# SCH_WINGLET_DEBUG.net
KiCad netlist of a schematic drawn in Altium Designer
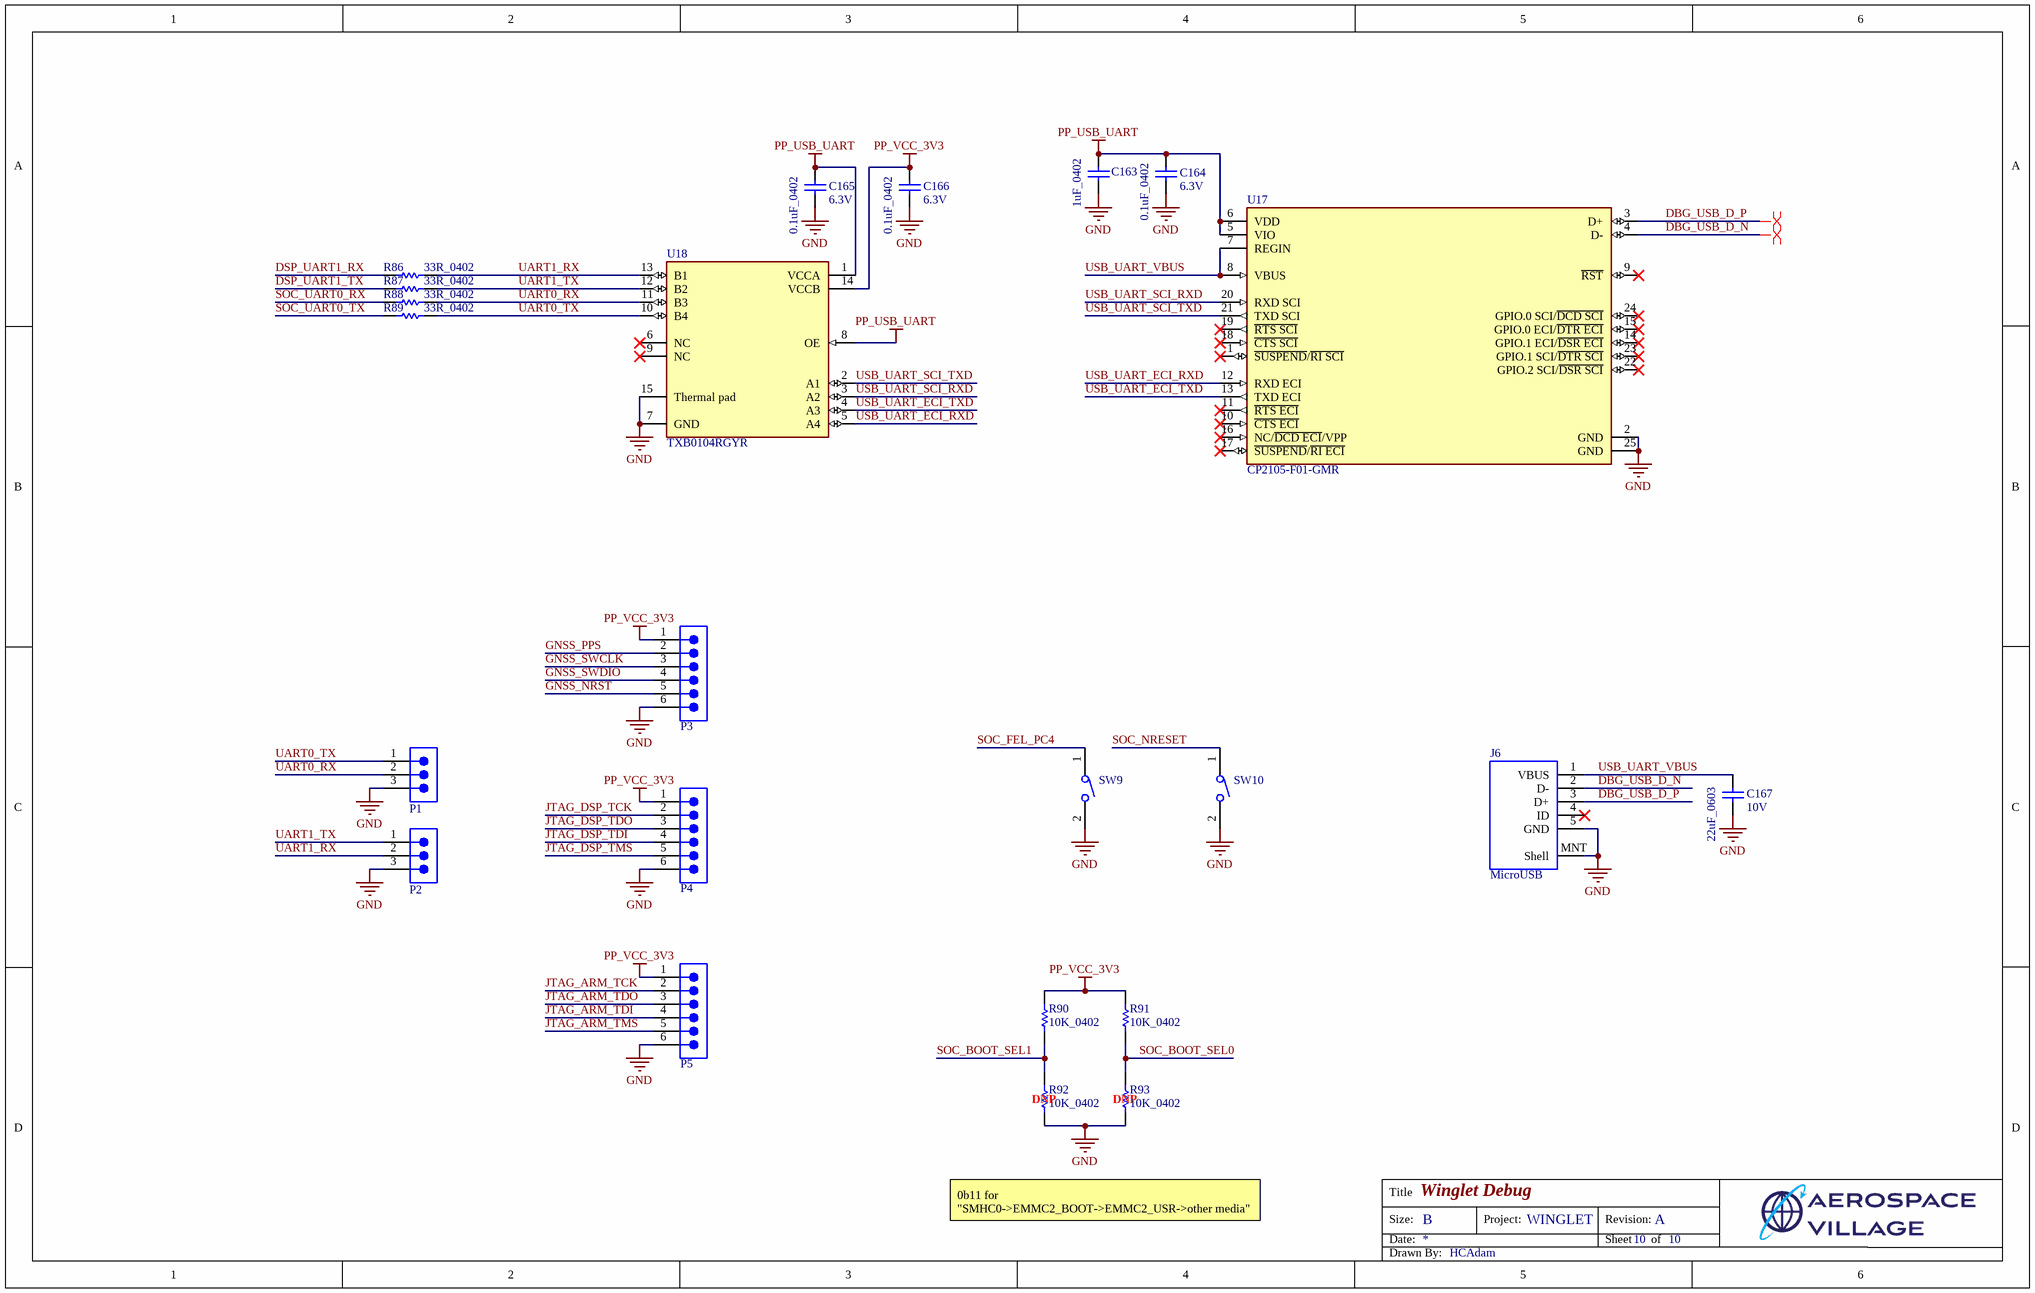
[diagram p0: SCH_WINGLET_DEBUG.SchDoc]

(export (version "E")
  (design (tool "Eeschema 10.0.6"))
  (components
    (comp (ref "C163")
      (value "1uF_0402")
      (footprint "CAPC1005X55X25NL5T10")
      (fields (field (name "TOLERANCE") "10%") (field (name "PARTNUMBER") "GRM155R60J105KE19D"))
      (libsource (lib "Altium Content Vault") (part "CAP-NP-2"))
    )
    (comp (ref "C164")
      (value "0.1uF_0402")
      (footprint "CAPC1005X56X25NL10T15")
      (description "04026D104KAT2A")
      (fields (field (name "MANUFACTURER") "AVX Interconnect / Elco") (field (name "VOLTAGE RATING") "6.3V"))
      (libsource (lib "Altium Content Vault") (part "CAP"))
    )
    (comp (ref "C165")
      (value "0.1uF_0402")
      (footprint "CAPC1005X56X25NL10T15")
      (description "04026D104KAT2A")
      (fields (field (name "MANUFACTURER") "AVX Interconnect / Elco") (field (name "VOLTAGE RATING") "6.3V"))
      (libsource (lib "Altium Content Vault") (part "CAP"))
    )
    (comp (ref "C166")
      (value "0.1uF_0402")
      (footprint "CAPC1005X56X25NL10T15")
      (description "04026D104KAT2A")
      (fields (field (name "MANUFACTURER") "AVX Interconnect / Elco") (field (name "VOLTAGE RATING") "6.3V"))
      (libsource (lib "Altium Content Vault") (part "CAP"))
    )
    (comp (ref "C167")
      (value "22uF_0603")
      (footprint "CAPC1608X100X20NL10")
      (fields
        (field (name "MANUFACTURER") "TDK")
        (field (name "TOLERANCE") "±20%")
        (field (name "PCN PART NUMBER") "MLCCPartNumberChange30/Nov/2012")
        (field (name "VOLTAGE RATING") "10V")
      )
      (libsource (lib "Altium Content Vault") (part "CAP-NP-2"))
    )
    (comp (ref "J6")
      (value "MicroUSB")
      (footprint "LCSC_MicroQTJ")
      (description "MicroQTJ MicroUSB CONN")
      (libsource (lib "DCAV32_WINGLET_SCHLIB") (part "MicroQTJ"))
    )
    (comp (ref "P1")
      (value "TSW-103-07-G-S")
      (footprint "SMTC-TSW-103-07-X-S")
      (description "0.025\" SQ Post Header, Through-hole, Vertical, -55 to 125 degC, 2.54 mm Pitch, 3-Pin, Male, RoHS")
      (fields (field (name "MANUFACTURER") "Samtec"))
      (libsource (lib "Altium Content Vault") (part "SMTC-TSW-103-X-X-S-X"))
    )
    (comp (ref "P2")
      (value "TSW-103-07-G-S")
      (footprint "SMTC-TSW-103-07-X-S")
      (description "0.025\" SQ Post Header, Through-hole, Vertical, -55 to 125 degC, 2.54 mm Pitch, 3-Pin, Male, RoHS")
      (fields (field (name "MANUFACTURER") "Samtec"))
      (libsource (lib "Altium Content Vault") (part "SMTC-TSW-103-X-X-S-X"))
    )
    (comp (ref "P3")
      (value "TSW-106-07-F-S")
      (footprint "SMTC-TSW-106-07-X-S")
      (description "0.025\" SQ Post Header, Through-hole, Vertical, -55 to 125 degC, 2.54 mm Pitch, 6-Pin, Male, RoHS")
      (fields (field (name "MANUFACTURER") "Samtec"))
      (libsource (lib "Altium Content Vault") (part "SMTC-TSW-106-X-X-S-X"))
    )
    (comp (ref "P4")
      (value "TSW-106-07-F-S")
      (footprint "SMTC-TSW-106-07-X-S")
      (description "0.025\" SQ Post Header, Through-hole, Vertical, -55 to 125 degC, 2.54 mm Pitch, 6-Pin, Male, RoHS")
      (fields (field (name "MANUFACTURER") "Samtec"))
      (libsource (lib "Altium Content Vault") (part "SMTC-TSW-106-X-X-S-X"))
    )
    (comp (ref "P5")
      (value "TSW-106-07-F-S")
      (footprint "SMTC-TSW-106-07-X-S")
      (description "0.025\" SQ Post Header, Through-hole, Vertical, -55 to 125 degC, 2.54 mm Pitch, 6-Pin, Male, RoHS")
      (fields (field (name "MANUFACTURER") "Samtec"))
      (libsource (lib "Altium Content Vault") (part "SMTC-TSW-106-X-X-S-X"))
    )
    (comp (ref "R86")
      (value "33R_0402")
      (footprint "RESC1005X40X25NL05T05")
      (description "ERJ2RKF33R0X")
      (fields (field (name "MANUFACTURER") "Panasonic"))
      (libsource (lib "Altium Content Vault") (part "RES"))
    )
    (comp (ref "R87")
      (value "33R_0402")
      (footprint "RESC1005X40X25NL05T05")
      (description "ERJ2RKF33R0X")
      (fields (field (name "MANUFACTURER") "Panasonic"))
      (libsource (lib "Altium Content Vault") (part "RES"))
    )
    (comp (ref "R88")
      (value "33R_0402")
      (footprint "RESC1005X40X25NL05T05")
      (description "ERJ2RKF33R0X")
      (fields (field (name "MANUFACTURER") "Panasonic"))
      (libsource (lib "Altium Content Vault") (part "RES"))
    )
    (comp (ref "R89")
      (value "33R_0402")
      (footprint "RESC1005X40X25NL05T05")
      (description "ERJ2RKF33R0X")
      (fields (field (name "MANUFACTURER") "Panasonic"))
      (libsource (lib "Altium Content Vault") (part "RES"))
    )
    (comp (ref "R90")
      (value "10K_0402")
      (footprint "RESC1005X40X25NL05T05")
      (fields (field (name "TOLERANCE") "1%") (field (name "MANUFACTURER") "Panasonic"))
      (libsource (lib "Altium Content Vault") (part "RES-2"))
    )
    (comp (ref "R91")
      (value "10K_0402")
      (footprint "RESC1005X40X25NL05T05")
      (fields (field (name "TOLERANCE") "1%") (field (name "MANUFACTURER") "Panasonic"))
      (libsource (lib "Altium Content Vault") (part "RES-2"))
    )
    (comp (ref "R92")
      (value "10K_0402")
      (footprint "RESC1005X40X25NL05T05")
      (fields
        (field (name "TOLERANCE") "1%")
        (field (name "MANUFACTURER") "Panasonic")
        (field (name "DNP") "DNP")
      )
      (libsource (lib "Altium Content Vault") (part "RES-2"))
    )
    (comp (ref "R93")
      (value "10K_0402")
      (footprint "RESC1005X40X25NL05T05")
      (fields
        (field (name "TOLERANCE") "1%")
        (field (name "MANUFACTURER") "Panasonic")
        (field (name "DNP") "DNP")
      )
      (libsource (lib "Altium Content Vault") (part "RES-2"))
    )
    (comp (ref "SW9")
      (value "GT-TC029B-H025-L1N")
      (footprint "LCSC_SMD_SW_SMALL")
      (description "SMD SPST Tactile Switch\r\nC843669")
      (libsource (lib "DCAV32_WINGLET_SCHLIB") (part "GT-TC029B-H025-L1N"))
    )
    (comp (ref "SW10")
      (value "GT-TC029B-H025-L1N")
      (footprint "LCSC_SMD_SW_SMALL")
      (description "SMD SPST Tactile Switch\r\nC843669")
      (libsource (lib "DCAV32_WINGLET_SCHLIB") (part "GT-TC029B-H025-L1N"))
    )
    (comp (ref "U17")
      (value "CP2105-F01-GMR")
      (footprint "FP-CP2105-F01-GMR-MFG")
      (description "IC SGL USB-DL UART BRIDGE 24QFN")
      (fields
        (field (name "MANUFACTURER") "Silicon Labs")
        (field (name "OCTOPART") "https://octopart.com/cp2105-f01-gmr-silicon+labs-19668643")
      )
      (libsource (lib "Altium Content Vault") (part "1947c35c85b0d61e04dffc410a2c8d9"))
    )
    (comp (ref "U18")
      (value "TXB0104RGYR")
      (footprint "FP-RGY0014A-MFG")
      (description "IC TRNSLTR BIDIRECTIONAL 14VQFN")
      (fields
        (field (name "MANUFACTURER") "Texas Instruments")
        (field (name "OCTOPART") "https://octopart.com/txb0104rgyr-texas+instruments-1485948")
      )
      (libsource (lib "Altium Content Vault") (part "00c1e25395d90d543401131e0a6fef8"))
    )
  )
  (nets
    (net (code "1") (name "/DBG_USB_D_N") (class "Default")
      (node (ref "J6") (pin "2") (pinfunction "D-_2") (pintype "passive"))
      (node (ref "U17") (pin "4") (pinfunction "D-_4") (pintype "bidirectional"))
    )
    (net (code "2") (name "/DBG_USB_D_P") (class "Default")
      (node (ref "J6") (pin "3") (pinfunction "D+_3") (pintype "passive"))
      (node (ref "U17") (pin "3") (pinfunction "D+_3") (pintype "bidirectional"))
    )
    (net (code "3") (name "/DSP_UART1_RX") (class "Default")
      (node (ref "R86") (pin "1") (pinfunction "1_1") (pintype "passive"))
    )
    (net (code "4") (name "/DSP_UART1_TX") (class "Default")
      (node (ref "R87") (pin "1") (pinfunction "1_1") (pintype "passive"))
    )
    (net (code "5") (name "/GNSS_NRST") (class "Default")
      (node (ref "P3") (pin "5") (pinfunction "5_5") (pintype "passive"))
    )
    (net (code "6") (name "/GNSS_PPS") (class "Default")
      (node (ref "P3") (pin "2") (pinfunction "2_2") (pintype "passive"))
    )
    (net (code "7") (name "/GNSS_SWCLK") (class "Default")
      (node (ref "P3") (pin "3") (pinfunction "3_3") (pintype "passive"))
    )
    (net (code "8") (name "/GNSS_SWDIO") (class "Default")
      (node (ref "P3") (pin "4") (pinfunction "4_4") (pintype "passive"))
    )
    (net (code "9") (name "/JTAG_ARM_TCK") (class "Default")
      (node (ref "P5") (pin "2") (pinfunction "2_2") (pintype "passive"))
    )
    (net (code "10") (name "/JTAG_ARM_TDI") (class "Default")
      (node (ref "P5") (pin "4") (pinfunction "4_4") (pintype "passive"))
    )
    (net (code "11") (name "/JTAG_ARM_TDO") (class "Default")
      (node (ref "P5") (pin "3") (pinfunction "3_3") (pintype "passive"))
    )
    (net (code "12") (name "/JTAG_ARM_TMS") (class "Default")
      (node (ref "P5") (pin "5") (pinfunction "5_5") (pintype "passive"))
    )
    (net (code "13") (name "/JTAG_DSP_TCK") (class "Default")
      (node (ref "P4") (pin "2") (pinfunction "2_2") (pintype "passive"))
    )
    (net (code "14") (name "/JTAG_DSP_TDI") (class "Default")
      (node (ref "P4") (pin "4") (pinfunction "4_4") (pintype "passive"))
    )
    (net (code "15") (name "/JTAG_DSP_TDO") (class "Default")
      (node (ref "P4") (pin "3") (pinfunction "3_3") (pintype "passive"))
    )
    (net (code "16") (name "/JTAG_DSP_TMS") (class "Default")
      (node (ref "P4") (pin "5") (pinfunction "5_5") (pintype "passive"))
    )
    (net (code "17") (name "/SOC_BOOT_SEL0") (class "Default")
      (node (ref "R91") (pin "2") (pinfunction "2_2") (pintype "passive"))
      (node (ref "R93") (pin "1") (pinfunction "1_1") (pintype "passive"))
    )
    (net (code "18") (name "/SOC_BOOT_SEL1") (class "Default")
      (node (ref "R90") (pin "2") (pinfunction "2_2") (pintype "passive"))
      (node (ref "R92") (pin "1") (pinfunction "1_1") (pintype "passive"))
    )
    (net (code "19") (name "/SOC_FEL_PC4") (class "Default") (node (ref "SW9") (pin "1") (pintype "passive")))
    (net (code "20") (name "/SOC_NRESET") (class "Default") (node (ref "SW10") (pin "1") (pintype "passive")))
    (net (code "21") (name "/SOC_UART0_RX") (class "Default")
      (node (ref "R88") (pin "1") (pinfunction "1_1") (pintype "passive"))
    )
    (net (code "22") (name "/SOC_UART0_TX") (class "Default")
      (node (ref "R89") (pin "1") (pinfunction "1_1") (pintype "passive"))
    )
    (net (code "23") (name "/UART0_RX") (class "Default")
      (node (ref "P1") (pin "2") (pinfunction "2_2") (pintype "passive"))
      (node (ref "R88") (pin "2") (pinfunction "2_2") (pintype "passive"))
      (node (ref "U18") (pin "11") (pinfunction "B3_11") (pintype "bidirectional"))
    )
    (net (code "24") (name "/UART0_TX") (class "Default")
      (node (ref "P1") (pin "1") (pinfunction "1_1") (pintype "passive"))
      (node (ref "R89") (pin "2") (pinfunction "2_2") (pintype "passive"))
      (node (ref "U18") (pin "10") (pinfunction "B4_10") (pintype "bidirectional"))
    )
    (net (code "25") (name "/UART1_RX") (class "Default")
      (node (ref "P2") (pin "2") (pinfunction "2_2") (pintype "passive"))
      (node (ref "R86") (pin "2") (pinfunction "2_2") (pintype "passive"))
      (node (ref "U18") (pin "13") (pinfunction "B1_13") (pintype "bidirectional"))
    )
    (net (code "26") (name "/UART1_TX") (class "Default")
      (node (ref "P2") (pin "1") (pinfunction "1_1") (pintype "passive"))
      (node (ref "R87") (pin "2") (pinfunction "2_2") (pintype "passive"))
      (node (ref "U18") (pin "12") (pinfunction "B2_12") (pintype "bidirectional"))
    )
    (net (code "27") (name "/USB_UART_ECI_RXD") (class "Default")
      (node (ref "U17") (pin "12") (pinfunction "RXD_ECI_12") (pintype "input"))
      (node (ref "U18") (pin "5") (pinfunction "A4_5") (pintype "bidirectional"))
    )
    (net (code "28") (name "/USB_UART_ECI_TXD") (class "Default")
      (node (ref "U17") (pin "13") (pinfunction "TXD_ECI_13") (pintype "output"))
      (node (ref "U18") (pin "4") (pinfunction "A3_4") (pintype "bidirectional"))
    )
    (net (code "29") (name "/USB_UART_SCI_RXD") (class "Default")
      (node (ref "U17") (pin "20") (pinfunction "RXD_SCI_20") (pintype "input"))
      (node (ref "U18") (pin "3") (pinfunction "A2_3") (pintype "bidirectional"))
    )
    (net (code "30") (name "/USB_UART_SCI_TXD") (class "Default")
      (node (ref "U17") (pin "21") (pinfunction "TXD_SCI_21") (pintype "output"))
      (node (ref "U18") (pin "2") (pinfunction "A1_2") (pintype "bidirectional"))
    )
    (net (code "31") (name "/USB_UART_VBUS") (class "Default")
      (node (ref "C167") (pin "2") (pinfunction "2_2") (pintype "passive"))
      (node (ref "J6") (pin "1") (pinfunction "VBUS_1") (pintype "passive"))
      (node (ref "U17") (pin "7") (pinfunction "REGIN_7") (pintype "power_in"))
      (node (ref "U17") (pin "8") (pinfunction "VBUS_8") (pintype "input"))
    )
    (net (code "32") (name "GND") (class "Default")
      (node (ref "C163") (pin "1") (pinfunction "1_1") (pintype "passive"))
      (node (ref "C164") (pin "1") (pinfunction "1_1") (pintype "passive"))
      (node (ref "C165") (pin "1") (pinfunction "1_1") (pintype "passive"))
      (node (ref "C166") (pin "1") (pinfunction "1_1") (pintype "passive"))
      (node (ref "C167") (pin "1") (pinfunction "1_1") (pintype "passive"))
      (node (ref "J6") (pin "5") (pinfunction "GND_5") (pintype "passive"))
      (node (ref "J6") (pin "MNT") (pinfunction "Shell_MNT") (pintype "passive"))
      (node (ref "P1") (pin "3") (pinfunction "3_3") (pintype "passive"))
      (node (ref "P2") (pin "3") (pinfunction "3_3") (pintype "passive"))
      (node (ref "P3") (pin "6") (pinfunction "6_6") (pintype "passive"))
      (node (ref "P4") (pin "6") (pinfunction "6_6") (pintype "passive"))
      (node (ref "P5") (pin "6") (pinfunction "6_6") (pintype "passive"))
      (node (ref "R92") (pin "2") (pinfunction "2_2") (pintype "passive"))
      (node (ref "R93") (pin "2") (pinfunction "2_2") (pintype "passive"))
      (node (ref "SW10") (pin "2") (pintype "passive"))
      (node (ref "SW9") (pin "2") (pintype "passive"))
      (node (ref "U17") (pin "2") (pinfunction "GND_2") (pintype "power_in"))
      (node (ref "U17") (pin "25") (pinfunction "GND_25") (pintype "power_in"))
      (node (ref "U18") (pin "15") (pinfunction "Thermal_pad_15") (pintype "power_in"))
      (node (ref "U18") (pin "7") (pinfunction "GND_7") (pintype "power_in"))
    )
    (net (code "33") (name "PP_USB_UART") (class "Default")
      (node (ref "C163") (pin "2") (pinfunction "2_2") (pintype "passive"))
      (node (ref "C164") (pin "2") (pinfunction "2_2") (pintype "passive"))
      (node (ref "C165") (pin "2") (pinfunction "2_2") (pintype "passive"))
      (node (ref "U17") (pin "5") (pinfunction "VIO_5") (pintype "power_in"))
      (node (ref "U17") (pin "6") (pinfunction "VDD_6") (pintype "power_in"))
      (node (ref "U18") (pin "1") (pinfunction "VCCA_1") (pintype "power_in"))
      (node (ref "U18") (pin "8") (pinfunction "OE_8") (pintype "input"))
    )
    (net (code "34") (name "PP_VCC_3V3") (class "Default")
      (node (ref "C166") (pin "2") (pinfunction "2_2") (pintype "passive"))
      (node (ref "P3") (pin "1") (pinfunction "1_1") (pintype "passive"))
      (node (ref "P4") (pin "1") (pinfunction "1_1") (pintype "passive"))
      (node (ref "P5") (pin "1") (pinfunction "1_1") (pintype "passive"))
      (node (ref "R90") (pin "1") (pinfunction "1_1") (pintype "passive"))
      (node (ref "R91") (pin "1") (pinfunction "1_1") (pintype "passive"))
      (node (ref "U18") (pin "14") (pinfunction "VCCB_14") (pintype "power_in"))
    )
    (net (code "35") (name "unconnected-(J6-ID-Pad4)") (class "Default")
      (node (ref "J6") (pin "4") (pinfunction "ID_4") (pintype "passive+no_connect"))
    )
    (net (code "36") (name "unconnected-(U17-GPIO.0_ECI{slash}~{DTR_ECI}-Pad15)") (class "Default")
      (node (ref "U17") (pin "15") (pinfunction "GPIO.0_ECI/~{DTR_ECI}_15") (pintype "bidirectional+no_connect"))
    )
    (net (code "37") (name "unconnected-(U17-GPIO.0_SCI{slash}~{DCD_SCI}-Pad24)") (class "Default")
      (node (ref "U17") (pin "24") (pinfunction "GPIO.0_SCI/~{DCD_SCI}_24") (pintype "bidirectional+no_connect"))
    )
    (net (code "38") (name "unconnected-(U17-GPIO.1_ECI{slash}~{DSR_ECI}-Pad14)") (class "Default")
      (node (ref "U17") (pin "14") (pinfunction "GPIO.1_ECI/~{DSR_ECI}_14") (pintype "bidirectional+no_connect"))
    )
    (net (code "39") (name "unconnected-(U17-GPIO.1_SCI{slash}~{DTR_SCI}-Pad23)") (class "Default")
      (node (ref "U17") (pin "23") (pinfunction "GPIO.1_SCI/~{DTR_SCI}_23") (pintype "bidirectional+no_connect"))
    )
    (net (code "40") (name "unconnected-(U17-GPIO.2_SCI{slash}~{DSR_SCI}-Pad22)") (class "Default")
      (node (ref "U17") (pin "22") (pinfunction "GPIO.2_SCI/~{DSR_SCI}_22") (pintype "bidirectional+no_connect"))
    )
    (net (code "41") (name "unconnected-(U17-NC{slash}~{DCD_ECI}{slash}VPP-Pad16)") (class "Default")
      (node (ref "U17") (pin "16") (pinfunction "NC/~{DCD_ECI}/VPP_16") (pintype "input+no_connect"))
    )
    (net (code "42") (name "unconnected-(U17-~{CTS_ECI}-Pad10)") (class "Default")
      (node (ref "U17") (pin "10") (pinfunction "~{CTS_ECI}_10") (pintype "input+no_connect"))
    )
    (net (code "43") (name "unconnected-(U17-~{CTS_SCI}-Pad18)") (class "Default")
      (node (ref "U17") (pin "18") (pinfunction "~{CTS_SCI}_18") (pintype "input+no_connect"))
    )
    (net (code "44") (name "unconnected-(U17-~{RST}-Pad9)") (class "Default")
      (node (ref "U17") (pin "9") (pinfunction "~{RST}_9") (pintype "bidirectional+no_connect"))
    )
    (net (code "45") (name "unconnected-(U17-~{RTS_ECI}-Pad11)") (class "Default")
      (node (ref "U17") (pin "11") (pinfunction "~{RTS_ECI}_11") (pintype "output+no_connect"))
    )
    (net (code "46") (name "unconnected-(U17-~{RTS_SCI}-Pad19)") (class "Default")
      (node (ref "U17") (pin "19") (pinfunction "~{RTS_SCI}_19") (pintype "output+no_connect"))
    )
    (net (code "47") (name "unconnected-(U17-~{SUSPEND}{slash}~{RI_ECI}-Pad17)") (class "Default")
      (node (ref "U17") (pin "17") (pinfunction "~{SUSPEND}/~{RI_ECI}_17") (pintype "bidirectional+no_connect"))
    )
    (net (code "48") (name "unconnected-(U17-~{SUSPEND}{slash}~{RI_SCI}-Pad1)") (class "Default")
      (node (ref "U17") (pin "1") (pinfunction "~{SUSPEND}/~{RI_SCI}_1") (pintype "bidirectional+no_connect"))
    )
    (net (code "49") (name "unconnected-(U18-NC-Pad6)") (class "Default")
      (node (ref "U18") (pin "6") (pinfunction "NC_6") (pintype "passive+no_connect"))
    )
    (net (code "50") (name "unconnected-(U18-NC-Pad9)") (class "Default")
      (node (ref "U18") (pin "9") (pinfunction "NC_9") (pintype "passive+no_connect"))
    )
  )
)
